# ETH_PCIE_PHY.net
KiCad netlist of a schematic drawn in Altium Designer
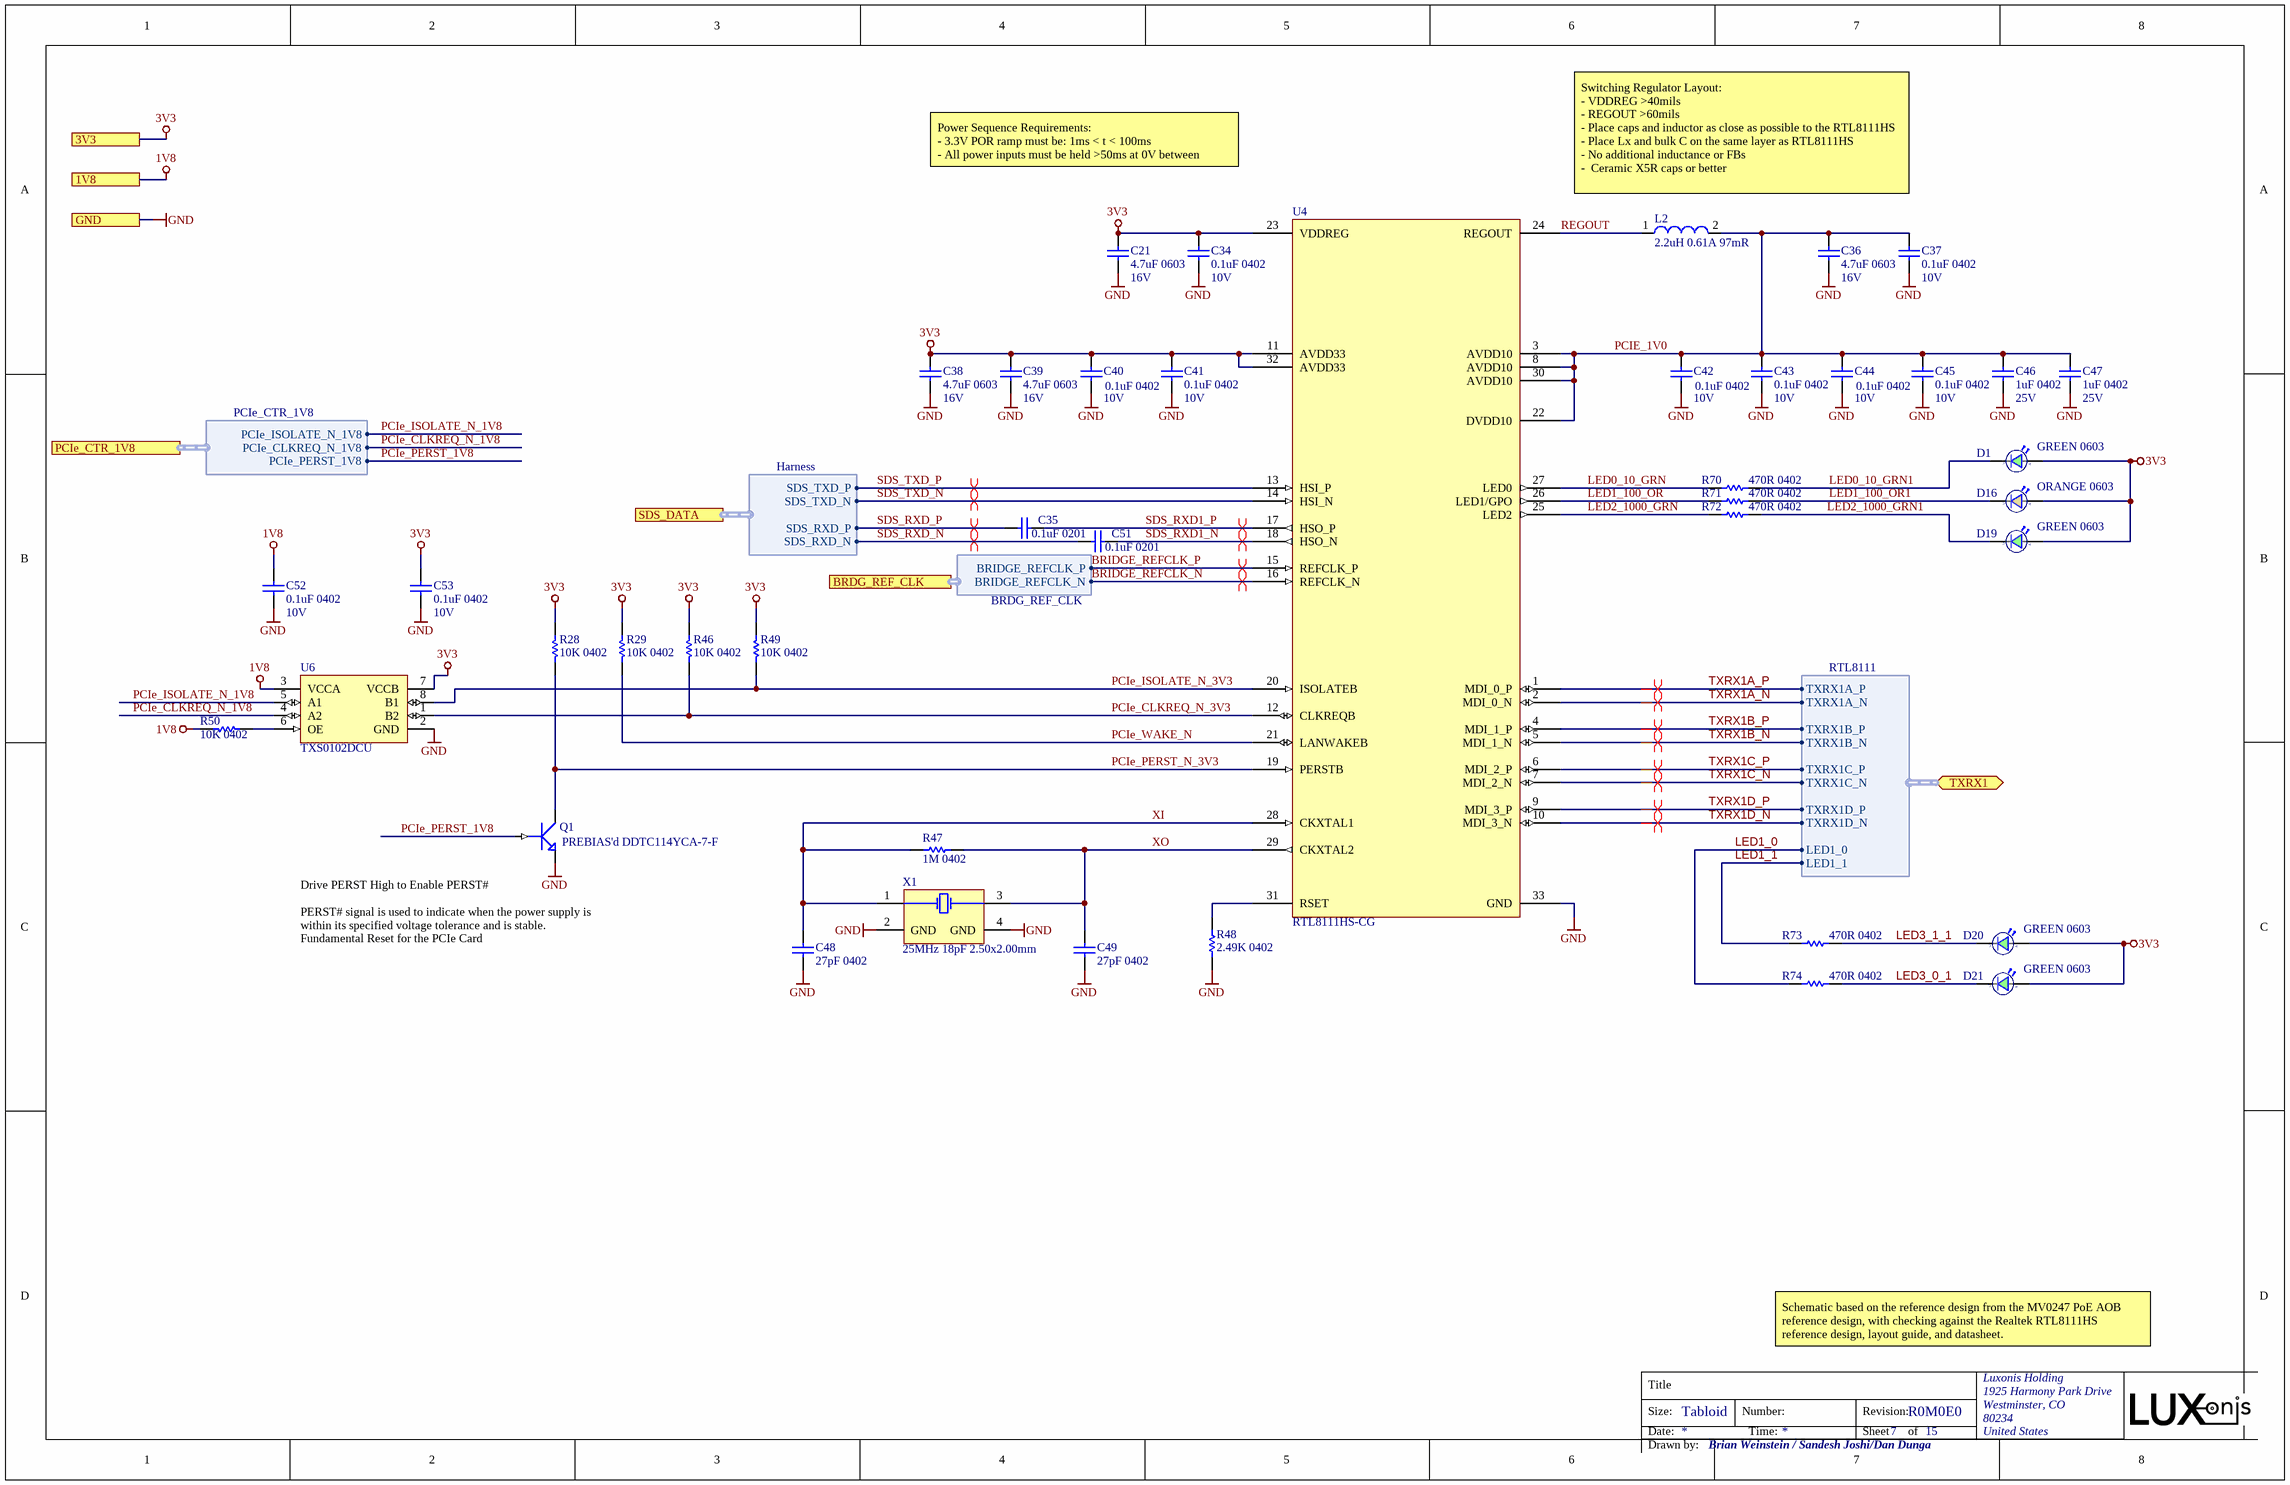
[diagram p0: ETH_PCIE_PHY.SchDoc]

(export (version "E")
  (design (tool "Eeschema 10.0.6"))
  (components
    (comp (ref "C21")
      (value "4.7uF 0603")
      (footprint "CAPC0603(1608)100_N")
      (description "CAP CER 4.7UF 16V X5R 0603 10%")
      (fields (field (name "TOLERANCE") "10%") (field (name "VOLTAGE RATING") "16V"))
      (libsource (lib "LuxonisMaster") (part "GRM188R61C475KAAJD"))
    )
    (comp (ref "C34")
      (value "0.1uF 0402")
      (footprint "CAP_Altium_Vault_Generic:CAPC0402(1005)70_N")
      (description "CAP CER 0.1UF 10V X7R 0402 5%")
      (fields (field (name "TOLERANCE") "5%") (field (name "VOLTAGE RATING") "10V"))
      (libsource (lib "LuxonisMaster") (part "GRM155R71A104JA01D"))
    )
    (comp (ref "C35")
      (value "0.1uF 0201")
      (footprint "CAP_Altium_Vault_Generic:CAPC0201(0603)33_L")
      (description "CAP CER 0.1UF 10V X5R 0201")
      (fields (field (name "TOLERANCE") "10%") (field (name "VOLTAGE") "10V"))
      (libsource (lib "LuxonisMaster") (part "GRM033R61A104KE15D"))
    )
    (comp (ref "C36")
      (value "4.7uF 0603")
      (footprint "CAPC0603(1608)100_N")
      (description "CAP CER 4.7UF 16V X5R 0603 10%")
      (fields (field (name "TOLERANCE") "10%") (field (name "VOLTAGE RATING") "16V"))
      (libsource (lib "LuxonisMaster") (part "GRM188R61C475KAAJD"))
    )
    (comp (ref "C37")
      (value "0.1uF 0402")
      (footprint "CAP_Altium_Vault_Generic:CAPC0402(1005)70_N")
      (description "CAP CER 0.1UF 10V X7R 0402 5%")
      (fields (field (name "TOLERANCE") "5%") (field (name "VOLTAGE RATING") "10V"))
      (libsource (lib "LuxonisMaster") (part "GRM155R71A104JA01D"))
    )
    (comp (ref "C38")
      (value "4.7uF 0603")
      (footprint "CAPC0603(1608)100_N")
      (description "CAP CER 4.7UF 16V X5R 0603 10%")
      (fields (field (name "TOLERANCE") "10%") (field (name "VOLTAGE RATING") "16V"))
      (libsource (lib "LuxonisMaster") (part "GRM188R61C475KAAJD"))
    )
    (comp (ref "C39")
      (value "4.7uF 0603")
      (footprint "CAPC0603(1608)100_N")
      (description "CAP CER 4.7UF 16V X5R 0603 10%")
      (fields (field (name "TOLERANCE") "10%") (field (name "VOLTAGE RATING") "16V"))
      (libsource (lib "LuxonisMaster") (part "GRM188R61C475KAAJD"))
    )
    (comp (ref "C40")
      (value "0.1uF 0402")
      (footprint "CAP_Altium_Vault_Generic:CAPC0402(1005)70_N")
      (description "CAP CER 0.1UF 10V X7R 0402 5%")
      (fields (field (name "TOLERANCE") "5%") (field (name "VOLTAGE RATING") "10V"))
      (libsource (lib "LuxonisMaster") (part "GRM155R71A104JA01D"))
    )
    (comp (ref "C41")
      (value "0.1uF 0402")
      (footprint "CAP_Altium_Vault_Generic:CAPC0402(1005)70_N")
      (description "CAP CER 0.1UF 10V X7R 0402 5%")
      (fields (field (name "TOLERANCE") "5%") (field (name "VOLTAGE RATING") "10V"))
      (libsource (lib "LuxonisMaster") (part "GRM155R71A104JA01D"))
    )
    (comp (ref "C42")
      (value "0.1uF 0402")
      (footprint "CAP_Altium_Vault_Generic:CAPC0402(1005)70_N")
      (description "CAP CER 0.1UF 10V X7R 0402 5%")
      (fields (field (name "TOLERANCE") "5%") (field (name "VOLTAGE RATING") "10V"))
      (libsource (lib "LuxonisMaster") (part "GRM155R71A104JA01D"))
    )
    (comp (ref "C43")
      (value "0.1uF 0402")
      (footprint "CAP_Altium_Vault_Generic:CAPC0402(1005)70_N")
      (description "CAP CER 0.1UF 10V X7R 0402 5%")
      (fields (field (name "TOLERANCE") "5%") (field (name "VOLTAGE RATING") "10V"))
      (libsource (lib "LuxonisMaster") (part "GRM155R71A104JA01D"))
    )
    (comp (ref "C44")
      (value "0.1uF 0402")
      (footprint "CAP_Altium_Vault_Generic:CAPC0402(1005)70_N")
      (description "CAP CER 0.1UF 10V X7R 0402 5%")
      (fields (field (name "TOLERANCE") "5%") (field (name "VOLTAGE RATING") "10V"))
      (libsource (lib "LuxonisMaster") (part "GRM155R71A104JA01D"))
    )
    (comp (ref "C45")
      (value "0.1uF 0402")
      (footprint "CAP_Altium_Vault_Generic:CAPC0402(1005)70_N")
      (description "CAP CER 0.1UF 10V X7R 0402 5%")
      (fields (field (name "TOLERANCE") "5%") (field (name "VOLTAGE RATING") "10V"))
      (libsource (lib "LuxonisMaster") (part "GRM155R71A104JA01D"))
    )
    (comp (ref "C46")
      (value "1uF 0402")
      (footprint "CAP_Altium_Vault_Generic:CAPC0402(1005)70_N")
      (description "CAP CER 1UF 25V X5R 0402 10%")
      (fields
        (field (name "TOLERANCE") "10%")
        (field (name "VOLTAGE") "25V")
        (field (name "VOLTAGE RATING") "25V")
      )
      (libsource (lib "LuxonisMaster") (part "GRM155R61E105KA12D"))
    )
    (comp (ref "C47")
      (value "1uF 0402")
      (footprint "CAP_Altium_Vault_Generic:CAPC0402(1005)70_N")
      (description "CAP CER 1UF 25V X5R 0402 10%")
      (fields
        (field (name "TOLERANCE") "10%")
        (field (name "VOLTAGE") "25V")
        (field (name "VOLTAGE RATING") "25V")
      )
      (libsource (lib "LuxonisMaster") (part "GRM155R61E105KA12D"))
    )
    (comp (ref "C48")
      (value "27pF 0402")
      (footprint "CAP_Altium_Vault_Generic:CAPC0402(1005)60_N")
      (description "CAP CER 27PF 50V C0G/NP0 0402")
      (fields (field (name "TOLERANCE") "5%") (field (name "VOLTAGE") "50V"))
      (libsource (lib "BW2098POE") (part "C0402C270J5GACTU"))
    )
    (comp (ref "C49")
      (value "27pF 0402")
      (footprint "CAP_Altium_Vault_Generic:CAPC0402(1005)60_N")
      (description "CAP CER 27PF 50V C0G/NP0 0402")
      (fields (field (name "TOLERANCE") "5%") (field (name "VOLTAGE") "50V"))
      (libsource (lib "BW2098POE") (part "C0402C270J5GACTU"))
    )
    (comp (ref "C51")
      (value "0.1uF 0201")
      (footprint "CAP_Altium_Vault_Generic:CAPC0201(0603)33_L")
      (description "CAP CER 0.1UF 10V X5R 0201")
      (fields (field (name "TOLERANCE") "10%") (field (name "VOLTAGE") "10V"))
      (libsource (lib "LuxonisMaster") (part "GRM033R61A104KE15D"))
    )
    (comp (ref "C52")
      (value "0.1uF 0402")
      (footprint "CAP_Altium_Vault_Generic:CAPC0402(1005)70_N")
      (description "CAP CER 0.1UF 10V X7R 0402 5%")
      (fields (field (name "TOLERANCE") "5%") (field (name "VOLTAGE RATING") "10V"))
      (libsource (lib "LuxonisMaster") (part "GRM155R71A104JA01D"))
    )
    (comp (ref "C53")
      (value "0.1uF 0402")
      (footprint "CAP_Altium_Vault_Generic:CAPC0402(1005)70_N")
      (description "CAP CER 0.1UF 10V X7R 0402 5%")
      (fields (field (name "TOLERANCE") "5%") (field (name "VOLTAGE RATING") "10V"))
      (libsource (lib "LuxonisMaster") (part "GRM155R71A104JA01D"))
    )
    (comp (ref "D1")
      (value "GREEN 0603")
      (footprint "SML_D1xx8W")
      (description "LED GREEN DIFFUSED 0603 SMD Green 572nm LED Indication - Discrete 2.2V 0603 (1608 Metric)")
      (fields (field (name "MANUFACTURER") "Rohm") (field (name "MANUFACTURER PART NUMBER") "SML-D12M8WT86"))
      (libsource (lib "LuxonisMaster") (part "SML-D12M8WT86"))
    )
    (comp (ref "D16")
      (value "ORANGE 0603")
      (footprint "LuxonisMaster:SML_D1xx8W")
      (description "LED ORANGE DIFFUSED 0603 SMD Orange 605nm LED Indication - Discrete 2.2V 0603 (1608 Metric)")
      (libsource (lib "LuxonisMaster") (part "SML-D12D8WT86"))
    )
    (comp (ref "D19")
      (value "GREEN 0603")
      (footprint "SML_D1xx8W")
      (description "LED GREEN DIFFUSED 0603 SMD Green 572nm LED Indication - Discrete 2.2V 0603 (1608 Metric)")
      (fields (field (name "MANUFACTURER") "Rohm") (field (name "MANUFACTURER PART NUMBER") "SML-D12M8WT86"))
      (libsource (lib "LuxonisMaster") (part "SML-D12M8WT86"))
    )
    (comp (ref "D20")
      (value "GREEN 0603")
      (footprint "SML_D1xx8W")
      (description "LED GREEN DIFFUSED 0603 SMD Green 572nm LED Indication - Discrete 2.2V 0603 (1608 Metric)")
      (fields (field (name "MANUFACTURER") "Rohm") (field (name "MANUFACTURER PART NUMBER") "SML-D12M8WT86"))
      (libsource (lib "LuxonisMaster") (part "SML-D12M8WT86"))
    )
    (comp (ref "D21")
      (value "GREEN 0603")
      (footprint "SML_D1xx8W")
      (description "LED GREEN DIFFUSED 0603 SMD Green 572nm LED Indication - Discrete 2.2V 0603 (1608 Metric)")
      (fields (field (name "MANUFACTURER") "Rohm") (field (name "MANUFACTURER PART NUMBER") "SML-D12M8WT86"))
      (libsource (lib "LuxonisMaster") (part "SML-D12M8WT86"))
    )
    (comp (ref "L2")
      (value "2.2uH 0.61A 97mR")
      (footprint "BW2098POE:LQH32NH2R2J23L")
      (description "FIXED IND 2.2UH 610MA 97MOHM SMD")
      (fields (field (name "TOLERANCE") "5%"))
      (libsource (lib "BW2098POE") (part "LQH32NH2R2J23L"))
    )
    (comp (ref "Q1")
      (value "PREBIAS'd DDTC114YCA-7-F")
      (footprint "BW2098POE:DDTC114YCA-7-F")
      (description "TRANS PREBIAS NPN 200MW SOT23-3")
      (libsource (lib "BW2098POE") (part "DDTC114YCA-7-F"))
    )
    (comp (ref "R28")
      (value "10K 0402")
      (footprint "RESC0402(1005)_N")
      (fields (field (name "TOLERANCE") "1%"))
      (libsource (lib "LuxonisMaster") (part "RC0402FR-1310KL"))
    )
    (comp (ref "R29")
      (value "10K 0402")
      (footprint "RESC0402(1005)_N")
      (fields (field (name "TOLERANCE") "1%"))
      (libsource (lib "LuxonisMaster") (part "RC0402FR-1310KL"))
    )
    (comp (ref "R46")
      (value "10K 0402")
      (footprint "RESC0402(1005)_N")
      (fields (field (name "TOLERANCE") "1%"))
      (libsource (lib "LuxonisMaster") (part "RC0402FR-1310KL"))
    )
    (comp (ref "R47")
      (value "1M 0402")
      (footprint "RESC0402(1005)_N")
      (description "RES SMD 1M OHM 1% 1/16W 0402")
      (fields (field (name "TOLERANCE") "1%"))
      (libsource (lib "LuxonisMaster") (part "RC0402FR-071ML"))
    )
    (comp (ref "R48")
      (value "2.49K 0402")
      (footprint "RESC0402(1005)_N")
      (description "RES SMD 2.49K OHM 1% 1/16W 0402")
      (fields (field (name "TOLERANCE") "1%"))
      (libsource (lib "BW2098POE") (part "RC0402FR-072K49L"))
    )
    (comp (ref "R49")
      (value "10K 0402")
      (footprint "RESC0402(1005)_N")
      (fields (field (name "TOLERANCE") "1%"))
      (libsource (lib "LuxonisMaster") (part "RC0402FR-1310KL"))
    )
    (comp (ref "R50")
      (value "10K 0402")
      (footprint "RESC0402(1005)_N")
      (fields (field (name "TOLERANCE") "1%"))
      (libsource (lib "LuxonisMaster") (part "RC0402FR-1310KL"))
    )
    (comp (ref "R70")
      (value "470R 0402")
      (footprint "RESC0402(1005)_N")
      (description "RES SMD 470 OHM 1% 1/16W 0402")
      (fields (field (name "TOLERANCE") "1%"))
      (libsource (lib "LuxonisMaster") (part "CRCW0402470RFKED"))
    )
    (comp (ref "R71")
      (value "470R 0402")
      (footprint "RESC0402(1005)_N")
      (description "RES SMD 470 OHM 1% 1/16W 0402")
      (fields (field (name "TOLERANCE") "1%"))
      (libsource (lib "LuxonisMaster") (part "CRCW0402470RFKED"))
    )
    (comp (ref "R72")
      (value "470R 0402")
      (footprint "RESC0402(1005)_N")
      (description "RES SMD 470 OHM 1% 1/16W 0402")
      (fields (field (name "TOLERANCE") "1%"))
      (libsource (lib "LuxonisMaster") (part "CRCW0402470RFKED"))
    )
    (comp (ref "R73")
      (value "470R 0402")
      (footprint "RESC0402(1005)_N")
      (description "RES SMD 470 OHM 1% 1/16W 0402")
      (fields (field (name "TOLERANCE") "1%"))
      (libsource (lib "LuxonisMaster") (part "CRCW0402470RFKED"))
    )
    (comp (ref "R74")
      (value "470R 0402")
      (footprint "RESC0402(1005)_N")
      (description "RES SMD 470 OHM 1% 1/16W 0402")
      (fields (field (name "TOLERANCE") "1%"))
      (libsource (lib "LuxonisMaster") (part "CRCW0402470RFKED"))
    )
    (comp (ref "U4")
      (value "RTL8111HS-CG")
      (footprint "BW2098POE:RTL8111Hx-CG")
      (description "IC ETHERNET/PCIe PHY Realtek")
      (libsource (lib "BW2098POE") (part "RTL8111HS"))
    )
    (comp (ref "U6")
      (value "TXS0102DCU")
      (footprint "BW2098POE:TXS0102DCUR")
      (description "TEXAS INSTRUMENTS - TXS0102DCUR - IC, TRANSLATOR, 2 BIT, BI, US-8")
      (libsource (lib "BW2098POE") (part "TXS0102DCUR"))
    )
    (comp (ref "X1")
      (value "25MHz 18pF 2.50x2.00mm")
      (footprint "BW2098POE:ECS-250-18-36B-CKY-TR")
      (description "CRYSTAL 25.0000MHZ 18PF SMD 25MHz ±10ppm Crystal 18pF 50 Ohms 4-SMD, No Lead")
      (libsource (lib "BW2098POE") (part "ECS-250-18-36B-CKY-TR"))
    )
  )
  (nets
    (net (code "5") (name "/BRIDGE_REFCLK_N") (class "Default")
      (node (ref "U4") (pin "16") (pinfunction "REFCLK_N_16") (pintype "input"))
    )
    (net (code "6") (name "/BRIDGE_REFCLK_P") (class "Default")
      (node (ref "U4") (pin "15") (pinfunction "REFCLK_P_15") (pintype "input"))
    )
    (net (code "7") (name "/LED0_10_GRN") (class "Default")
      (node (ref "R70") (pin "1") (pinfunction "1_1") (pintype "passive"))
      (node (ref "U4") (pin "27") (pinfunction "LED0_27") (pintype "output"))
    )
    (net (code "8") (name "/LED0_10_GRN1") (class "Default")
      (node (ref "D1") (pin "1") (pinfunction "C_1") (pintype "passive"))
      (node (ref "R70") (pin "2") (pinfunction "2_2") (pintype "passive"))
    )
    (net (code "9") (name "/LED1_0") (class "Default")
      (node (ref "R74") (pin "1") (pinfunction "1_1") (pintype "passive"))
    )
    (net (code "10") (name "/LED1_1") (class "Default")
      (node (ref "R73") (pin "1") (pinfunction "1_1") (pintype "passive"))
    )
    (net (code "11") (name "/LED1_100_OR") (class "Default")
      (node (ref "R71") (pin "1") (pinfunction "1_1") (pintype "passive"))
      (node (ref "U4") (pin "26") (pinfunction "LED1/GPO_26") (pintype "output"))
    )
    (net (code "12") (name "/LED1_100_OR1") (class "Default")
      (node (ref "D16") (pin "1") (pinfunction "C_1") (pintype "passive"))
      (node (ref "R71") (pin "2") (pinfunction "2_2") (pintype "passive"))
    )
    (net (code "13") (name "/LED2_1000_GRN") (class "Default")
      (node (ref "R72") (pin "1") (pinfunction "1_1") (pintype "passive"))
      (node (ref "U4") (pin "25") (pinfunction "LED2_25") (pintype "output"))
    )
    (net (code "14") (name "/LED2_1000_GRN1") (class "Default")
      (node (ref "D19") (pin "1") (pinfunction "C_1") (pintype "passive"))
      (node (ref "R72") (pin "2") (pinfunction "2_2") (pintype "passive"))
    )
    (net (code "15") (name "/LED3_0_1") (class "Default")
      (node (ref "D21") (pin "1") (pinfunction "C_1") (pintype "passive"))
      (node (ref "R74") (pin "2") (pinfunction "2_2") (pintype "passive"))
    )
    (net (code "16") (name "/LED3_1_1") (class "Default")
      (node (ref "D20") (pin "1") (pinfunction "C_1") (pintype "passive"))
      (node (ref "R73") (pin "2") (pinfunction "2_2") (pintype "passive"))
    )
    (net (code "17") (name "/PCIE_1V0") (class "Default")
      (node (ref "C36") (pin "2") (pinfunction "2_2") (pintype "passive"))
      (node (ref "C37") (pin "2") (pinfunction "2_2") (pintype "passive"))
      (node (ref "C42") (pin "2") (pinfunction "2_2") (pintype "passive"))
      (node (ref "C43") (pin "2") (pinfunction "2_2") (pintype "passive"))
      (node (ref "C44") (pin "2") (pinfunction "2_2") (pintype "passive"))
      (node (ref "C45") (pin "2") (pinfunction "2_2") (pintype "passive"))
      (node (ref "C46") (pin "2") (pinfunction "2_2") (pintype "passive"))
      (node (ref "C47") (pin "2") (pinfunction "2_2") (pintype "passive"))
      (node (ref "L2") (pin "2") (pinfunction "2_2") (pintype "passive"))
      (node (ref "U4") (pin "22") (pinfunction "DVDD10_22") (pintype "passive"))
      (node (ref "U4") (pin "3") (pinfunction "AVDD10_3") (pintype "passive"))
      (node (ref "U4") (pin "30") (pinfunction "AVDD10_30") (pintype "passive"))
      (node (ref "U4") (pin "8") (pinfunction "AVDD10_8") (pintype "passive"))
    )
    (net (code "18") (name "/PCIe_CLKREQ_N_1V8") (class "Default")
      (node (ref "U6") (pin "4") (pinfunction "A2_4") (pintype "bidirectional"))
    )
    (net (code "19") (name "/PCIe_CLKREQ_N_3V3") (class "Default")
      (node (ref "R46") (pin "2") (pinfunction "2_2") (pintype "passive"))
      (node (ref "U4") (pin "12") (pinfunction "CLKREQB_12") (pintype "bidirectional"))
      (node (ref "U6") (pin "1") (pinfunction "B2_1") (pintype "bidirectional"))
    )
    (net (code "20") (name "/PCIe_ISOLATE_N_1V8") (class "Default")
      (node (ref "U6") (pin "5") (pinfunction "A1_5") (pintype "bidirectional"))
    )
    (net (code "21") (name "/PCIe_ISOLATE_N_3V3") (class "Default")
      (node (ref "R49") (pin "2") (pinfunction "2_2") (pintype "passive"))
      (node (ref "U4") (pin "20") (pinfunction "ISOLATEB_20") (pintype "input"))
      (node (ref "U6") (pin "8") (pinfunction "B1_8") (pintype "bidirectional"))
    )
    (net (code "22") (name "/PCIe_PERST_1V8") (class "Default")
      (node (ref "Q1") (pin "1") (pinfunction "B_1") (pintype "input"))
    )
    (net (code "23") (name "/PCIe_PERST_N_3V3") (class "Default")
      (node (ref "Q1") (pin "3") (pinfunction "C_3") (pintype "passive"))
      (node (ref "R28") (pin "2") (pinfunction "2_2") (pintype "passive"))
      (node (ref "U4") (pin "19") (pinfunction "PERSTB_19") (pintype "input"))
    )
    (net (code "24") (name "/PCIe_WAKE_N") (class "Default")
      (node (ref "R29") (pin "2") (pinfunction "2_2") (pintype "passive"))
      (node (ref "U4") (pin "21") (pinfunction "LANWAKEB_21") (pintype "bidirectional"))
    )
    (net (code "25") (name "/REGOUT") (class "Default")
      (node (ref "L2") (pin "1") (pinfunction "1_1") (pintype "passive"))
      (node (ref "U4") (pin "24") (pinfunction "REGOUT_24") (pintype "passive"))
    )
    (net (code "26") (name "/SDS_RXD1_N") (class "Default")
      (node (ref "C51") (pin "2") (pinfunction "2_2") (pintype "passive"))
      (node (ref "U4") (pin "18") (pinfunction "HSO_N_18") (pintype "output"))
    )
    (net (code "27") (name "/SDS_RXD1_P") (class "Default")
      (node (ref "C35") (pin "2") (pinfunction "2_2") (pintype "passive"))
      (node (ref "U4") (pin "17") (pinfunction "HSO_P_17") (pintype "output"))
    )
    (net (code "28") (name "/SDS_RXD_N") (class "Default")
      (node (ref "C51") (pin "1") (pinfunction "1_1") (pintype "passive"))
    )
    (net (code "29") (name "/SDS_RXD_P") (class "Default")
      (node (ref "C35") (pin "1") (pinfunction "1_1") (pintype "passive"))
    )
    (net (code "30") (name "/SDS_TXD_N") (class "Default")
      (node (ref "U4") (pin "14") (pinfunction "HSI_N_14") (pintype "input"))
    )
    (net (code "31") (name "/SDS_TXD_P") (class "Default")
      (node (ref "U4") (pin "13") (pinfunction "HSI_P_13") (pintype "input"))
    )
    (net (code "32") (name "/TXRX1A_N") (class "Default")
      (node (ref "U4") (pin "2") (pinfunction "MDI_0_N_2") (pintype "bidirectional"))
    )
    (net (code "33") (name "/TXRX1A_P") (class "Default")
      (node (ref "U4") (pin "1") (pinfunction "MDI_0_P_1") (pintype "bidirectional"))
    )
    (net (code "34") (name "/TXRX1B_N") (class "Default")
      (node (ref "U4") (pin "5") (pinfunction "MDI_1_N_5") (pintype "bidirectional"))
    )
    (net (code "35") (name "/TXRX1B_P") (class "Default")
      (node (ref "U4") (pin "4") (pinfunction "MDI_1_P_4") (pintype "bidirectional"))
    )
    (net (code "36") (name "/TXRX1C_N") (class "Default")
      (node (ref "U4") (pin "7") (pinfunction "MDI_2_N_7") (pintype "bidirectional"))
    )
    (net (code "37") (name "/TXRX1C_P") (class "Default")
      (node (ref "U4") (pin "6") (pinfunction "MDI_2_P_6") (pintype "bidirectional"))
    )
    (net (code "38") (name "/TXRX1D_N") (class "Default")
      (node (ref "U4") (pin "10") (pinfunction "MDI_3_N_10") (pintype "bidirectional"))
    )
    (net (code "39") (name "/TXRX1D_P") (class "Default")
      (node (ref "U4") (pin "9") (pinfunction "MDI_3_P_9") (pintype "bidirectional"))
    )
    (net (code "40") (name "/XI") (class "Default")
      (node (ref "C48") (pin "2") (pinfunction "2_2") (pintype "passive"))
      (node (ref "R47") (pin "1") (pinfunction "1_1") (pintype "passive"))
      (node (ref "U4") (pin "28") (pinfunction "CKXTAL1_28") (pintype "input"))
      (node (ref "X1") (pin "1") (pinfunction "X1_1") (pintype "passive"))
    )
    (net (code "41") (name "/XO") (class "Default")
      (node (ref "C49") (pin "2") (pinfunction "2_2") (pintype "passive"))
      (node (ref "R47") (pin "2") (pinfunction "2_2") (pintype "passive"))
      (node (ref "U4") (pin "29") (pinfunction "CKXTAL2_29") (pintype "output"))
      (node (ref "X1") (pin "3") (pinfunction "X2_3") (pintype "passive"))
    )
    (net (code "46") (name "1V8") (class "Default")
      (node (ref "C52") (pin "2") (pinfunction "2_2") (pintype "passive"))
      (node (ref "R50") (pin "2") (pinfunction "2_2") (pintype "passive"))
      (node (ref "U6") (pin "3") (pinfunction "VCCA_3") (pintype "power_in"))
    )
    (net (code "47") (name "3V3") (class "Default")
      (node (ref "C21") (pin "2") (pinfunction "2_2") (pintype "passive"))
      (node (ref "C34") (pin "2") (pinfunction "2_2") (pintype "passive"))
      (node (ref "C38") (pin "2") (pinfunction "2_2") (pintype "passive"))
      (node (ref "C39") (pin "2") (pinfunction "2_2") (pintype "passive"))
      (node (ref "C40") (pin "2") (pinfunction "2_2") (pintype "passive"))
      (node (ref "C41") (pin "2") (pinfunction "2_2") (pintype "passive"))
      (node (ref "C53") (pin "2") (pinfunction "2_2") (pintype "passive"))
      (node (ref "D1") (pin "2") (pinfunction "A_2") (pintype "passive"))
      (node (ref "D16") (pin "2") (pinfunction "A_2") (pintype "passive"))
      (node (ref "D19") (pin "2") (pinfunction "A_2") (pintype "passive"))
      (node (ref "D20") (pin "2") (pinfunction "A_2") (pintype "passive"))
      (node (ref "D21") (pin "2") (pinfunction "A_2") (pintype "passive"))
      (node (ref "R28") (pin "1") (pinfunction "1_1") (pintype "passive"))
      (node (ref "R29") (pin "1") (pinfunction "1_1") (pintype "passive"))
      (node (ref "R46") (pin "1") (pinfunction "1_1") (pintype "passive"))
      (node (ref "R49") (pin "1") (pinfunction "1_1") (pintype "passive"))
      (node (ref "U4") (pin "11") (pinfunction "AVDD33_11") (pintype "passive"))
      (node (ref "U4") (pin "23") (pinfunction "VDDREG_23") (pintype "passive"))
      (node (ref "U4") (pin "32") (pinfunction "AVDD33_32") (pintype "passive"))
      (node (ref "U6") (pin "7") (pinfunction "VCCB_7") (pintype "power_in"))
    )
    (net (code "48") (name "GND") (class "Default")
      (node (ref "C21") (pin "1") (pinfunction "1_1") (pintype "passive"))
      (node (ref "C34") (pin "1") (pinfunction "1_1") (pintype "passive"))
      (node (ref "C36") (pin "1") (pinfunction "1_1") (pintype "passive"))
      (node (ref "C37") (pin "1") (pinfunction "1_1") (pintype "passive"))
      (node (ref "C38") (pin "1") (pinfunction "1_1") (pintype "passive"))
      (node (ref "C39") (pin "1") (pinfunction "1_1") (pintype "passive"))
      (node (ref "C40") (pin "1") (pinfunction "1_1") (pintype "passive"))
      (node (ref "C41") (pin "1") (pinfunction "1_1") (pintype "passive"))
      (node (ref "C42") (pin "1") (pinfunction "1_1") (pintype "passive"))
      (node (ref "C43") (pin "1") (pinfunction "1_1") (pintype "passive"))
      (node (ref "C44") (pin "1") (pinfunction "1_1") (pintype "passive"))
      (node (ref "C45") (pin "1") (pinfunction "1_1") (pintype "passive"))
      (node (ref "C46") (pin "1") (pinfunction "1_1") (pintype "passive"))
      (node (ref "C47") (pin "1") (pinfunction "1_1") (pintype "passive"))
      (node (ref "C48") (pin "1") (pinfunction "1_1") (pintype "passive"))
      (node (ref "C49") (pin "1") (pinfunction "1_1") (pintype "passive"))
      (node (ref "C52") (pin "1") (pinfunction "1_1") (pintype "passive"))
      (node (ref "C53") (pin "1") (pinfunction "1_1") (pintype "passive"))
      (node (ref "Q1") (pin "2") (pinfunction "E_2") (pintype "passive"))
      (node (ref "R48") (pin "1") (pinfunction "1_1") (pintype "passive"))
      (node (ref "U4") (pin "33") (pinfunction "GND_33") (pintype "passive"))
      (node (ref "U6") (pin "2") (pinfunction "GND_2") (pintype "power_in"))
      (node (ref "X1") (pin "2") (pinfunction "GND_2") (pintype "power_in"))
      (node (ref "X1") (pin "4") (pinfunction "GND_4") (pintype "power_in"))
    )
    (net (code "49") (name "Net-(U4-RSET)") (class "Default")
      (node (ref "R48") (pin "2") (pinfunction "2_2") (pintype "passive"))
      (node (ref "U4") (pin "31") (pinfunction "RSET_31") (pintype "passive"))
    )
    (net (code "50") (name "Net-(U6-OE)") (class "Default")
      (node (ref "R50") (pin "1") (pinfunction "1_1") (pintype "passive"))
      (node (ref "U6") (pin "6") (pinfunction "OE_6") (pintype "input"))
    )
  )
)
